# led7SegDriverWithPS.net
KiCad netlist of a schematic drawn in Altium Designer
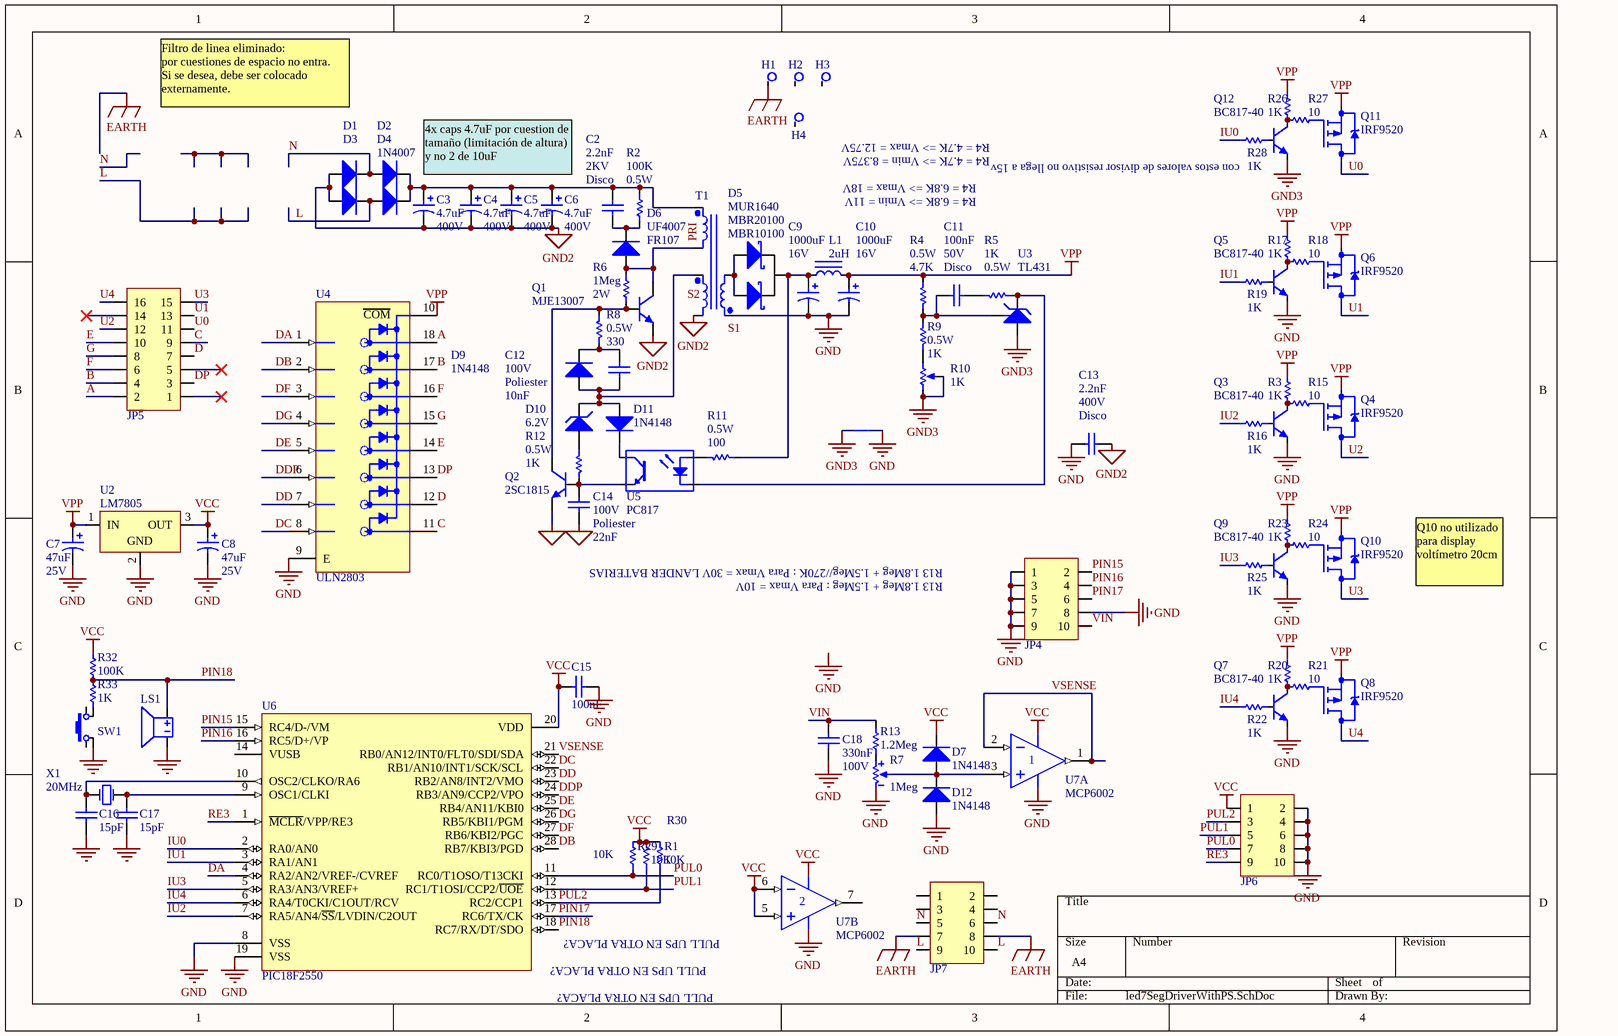
[diagram p0: led7SegDriverWithPS.SchDoc]

(export (version "E")
  (design (tool "Eeschema 10.0.6"))
  (components
    (comp (ref "C2")
      (value "2.2nF")
      (footprint "CAP200th")
      (description "Capacitor")
      (fields
        (field (name "VOLTAGE") "2KV")
        (field (name "TECHNOLOGY") "Disco")
        (field (name "Comment") "Cap")
      )
      (libsource (lib "FEDE") (part "Cap"))
    )
    (comp (ref "C3")
      (value "4.7uF")
      (footprint "cap10mm")
      (description "Capacitor Polarizado")
      (fields (field (name "VOLTAJE") "400V") (field (name "Comment") "Cap Pol"))
      (libsource (lib "FEDE") (part "Cap Pol"))
    )
    (comp (ref "C4")
      (value "4.7uF")
      (footprint "cap10mm")
      (description "Capacitor Polarizado")
      (fields (field (name "VOLTAJE") "400V") (field (name "Comment") "Cap Pol"))
      (libsource (lib "FEDE") (part "Cap Pol"))
    )
    (comp (ref "C5")
      (value "4.7uF")
      (footprint "cap10mm")
      (description "Capacitor Polarizado")
      (fields (field (name "VOLTAJE") "400V") (field (name "Comment") "Cap Pol"))
      (libsource (lib "FEDE") (part "Cap Pol"))
    )
    (comp (ref "C6")
      (value "4.7uF")
      (footprint "cap10mm")
      (description "Capacitor Polarizado")
      (fields (field (name "VOLTAJE") "400V") (field (name "Comment") "Cap Pol"))
      (libsource (lib "FEDE") (part "Cap Pol"))
    )
    (comp (ref "C7")
      (value "47uF")
      (footprint "Cap6.5mm")
      (description "Capacitor Polarizado")
      (fields (field (name "VOLTAJE") "25V") (field (name "Comment") "Cap Pol"))
      (libsource (lib "FEDE") (part "Cap Pol"))
    )
    (comp (ref "C8")
      (value "47uF")
      (footprint "Cap6.5mm")
      (description "Capacitor Polarizado")
      (fields (field (name "VOLTAJE") "25V") (field (name "Comment") "Cap Pol"))
      (libsource (lib "FEDE") (part "Cap Pol"))
    )
    (comp (ref "C9")
      (value "1000uF")
      (footprint "cap10mm")
      (description "Capacitor Polarizado")
      (fields (field (name "VOLTAJE") "16V") (field (name "Comment") "Cap Pol"))
      (libsource (lib "FEDE") (part "Cap Pol"))
    )
    (comp (ref "C10")
      (value "1000uF")
      (footprint "cap10mm")
      (description "Capacitor Polarizado")
      (fields (field (name "VOLTAJE") "16V") (field (name "Comment") "Cap Pol"))
      (libsource (lib "FEDE") (part "Cap Pol"))
    )
    (comp (ref "C11")
      (value "100nF")
      (footprint "C1206")
      (description "Capacitor")
      (fields
        (field (name "VOLTAGE") "50V")
        (field (name "TECHNOLOGY") "Disco")
        (field (name "Comment") "Cap")
      )
      (libsource (lib "FEDE") (part "Cap"))
    )
    (comp (ref "C12")
      (value "10nF")
      (footprint "CAP200th")
      (description "Capacitor")
      (fields
        (field (name "VOLTAGE") "100V")
        (field (name "TECHNOLOGY") "Poliester")
        (field (name "Comment") "Cap")
      )
      (libsource (lib "FEDE") (part "Cap"))
    )
    (comp (ref "C13")
      (value "2.2nF")
      (footprint "CAP200th")
      (description "Capacitor")
      (fields
        (field (name "VOLTAGE") "400V")
        (field (name "TECHNOLOGY") "Disco")
        (field (name "Comment") "Cap")
      )
      (libsource (lib "FEDE") (part "Cap"))
    )
    (comp (ref "C14")
      (value "22nF")
      (footprint "CAP200th")
      (description "Capacitor")
      (fields
        (field (name "VOLTAGE") "100V")
        (field (name "TECHNOLOGY") "Poliester")
        (field (name "Comment") "Cap")
      )
      (libsource (lib "FEDE") (part "Cap"))
    )
    (comp (ref "C15")
      (value "100nF")
      (footprint "1206NP")
      (description "Capacitor")
      (fields (field (name "VOLTAGE") "50V") (field (name "Comment") "Cap"))
      (libsource (lib "FEDE") (part "Cap"))
    )
    (comp (ref "C16")
      (value "15pF")
      (footprint "1206NP")
      (description "Capacitor")
      (fields (field (name "VOLTAGE") "50V") (field (name "Comment") "Cap"))
      (libsource (lib "FEDE") (part "Cap"))
    )
    (comp (ref "C17")
      (value "15pF")
      (footprint "1206NP")
      (description "Capacitor")
      (fields (field (name "VOLTAGE") "50V") (field (name "Comment") "Cap"))
      (libsource (lib "FEDE") (part "Cap"))
    )
    (comp (ref "C18")
      (value "330nF")
      (footprint "1206NP")
      (description "Capacitor")
      (fields (field (name "VOLTAGE") "100V") (field (name "Comment") "Cap"))
      (libsource (lib "FEDE") (part "Cap"))
    )
    (comp (ref "D1")
      (value "1N4007")
      (footprint "diode300_1mm")
      (description "1A 1000V General Purpose Rectifier")
      (libsource (lib "FEDE") (part "1N4007"))
    )
    (comp (ref "D2")
      (value "1N4007")
      (footprint "diode300_1mm")
      (description "1A 1000V General Purpose Rectifier")
      (libsource (lib "FEDE") (part "1N4007"))
    )
    (comp (ref "D3")
      (value "1N4007")
      (footprint "diode300_1mm")
      (description "1A 1000V General Purpose Rectifier")
      (libsource (lib "FEDE") (part "1N4007"))
    )
    (comp (ref "D4")
      (value "1N4007")
      (footprint "diode300_1mm")
      (description "1A 1000V General Purpose Rectifier")
      (libsource (lib "FEDE") (part "1N4007"))
    )
    (comp (ref "D5")
      (value "MBR20100")
      (footprint "TO220")
      (description "Schottky Diode 10A 45V")
      (fields (field (name "COMMENT2") "MBR10100") (field (name "ALTIUM_UNNAMED_1") "MUR1640"))
      (libsource (lib "FEDE") (part "MBR10100"))
    )
    (comp (ref "D6")
      (value "UF4007")
      (footprint "diode300_1mm")
      (description "1A 1000V General Purpose Rectifier")
      (fields (field (name "ALTERNATIVA") "FR107"))
      (libsource (lib "FEDE") (part "1N4007"))
    )
    (comp (ref "D7")
      (value "1N4148")
      (footprint "DSMD1MM")
      (description "High Conductance Fast Diode")
      (libsource (lib "FEDE") (part "1N4148"))
    )
    (comp (ref "D9")
      (value "1N4148")
      (footprint "DIODE300")
      (description "High Conductance Fast Diode")
      (libsource (lib "FEDE") (part "1N4148"))
    )
    (comp (ref "D10")
      (value "Zener")
      (footprint "DIODE300")
      (description "Zener Diode")
      (fields (field (name "VOLTAJE") "6.2V"))
      (libsource (lib "FEDE") (part "Zener"))
    )
    (comp (ref "D11")
      (value "1N4148")
      (footprint "DIODE300")
      (description "High Conductance Fast Diode")
      (libsource (lib "FEDE") (part "1N4148"))
    )
    (comp (ref "D12")
      (value "1N4148")
      (footprint "DSMD1MM")
      (description "High Conductance Fast Diode")
      (libsource (lib "FEDE") (part "1N4148"))
    )
    (comp (ref "H1")
      (value "Agujero de montaje")
      (footprint "agujero")
      (libsource (lib "FEDE") (part "Agujero de montaje"))
    )
    (comp (ref "H2")
      (value "Agujero de montaje")
      (footprint "agujero")
      (libsource (lib "FEDE") (part "Agujero de montaje"))
    )
    (comp (ref "H3")
      (value "Agujero de montaje")
      (footprint "agujero")
      (libsource (lib "FEDE") (part "Agujero de montaje"))
    )
    (comp (ref "H4")
      (value "Agujero de montaje")
      (footprint "agujero")
      (libsource (lib "FEDE") (part "Agujero de montaje"))
    )
    (comp (ref "JP4") (value "IDC 5x2") (footprint "idc5x2") (libsource (lib "FEDE") (part "IDC 5x2")))
    (comp (ref "JP5")
      (value "Header8x2")
      (footprint "idc8x2")
      (description "Header 8x2")
      (libsource (lib "FEDE") (part "Header8x2"))
    )
    (comp (ref "JP6") (value "IDC 5x2") (footprint "idc5x2") (libsource (lib "FEDE") (part "IDC 5x2")))
    (comp (ref "JP7") (value "IDC 5x2") (footprint "idc5x2") (libsource (lib "FEDE") (part "IDC 5x2")))
    (comp (ref "L1")
      (value "2uH")
      (footprint "ind8mm")
      (description "Inductor")
      (libsource (lib "FEDE") (part "Inductor"))
    )
    (comp (ref "LS1") (value "Buzzer") (footprint "buzzer12mm") (libsource (lib "FEDE") (part "Buzzer")))
    (comp (ref "Q1")
      (value "MJE13007")
      (footprint "TO220")
      (description "6A 100V NPN Bipolar Transistor")
      (libsource (lib "FEDE") (part "TIP41C"))
    )
    (comp (ref "Q2")
      (value "2SC1815")
      (footprint "to92")
      (description "NPN Bipolar Transistor")
      (libsource (lib "FEDE") (part "2SC1815"))
    )
    (comp (ref "Q3") (value "BC817-40") (footprint "SOT23") (libsource (lib "FEDE") (part "BC817-40")))
    (comp (ref "Q4")
      (value "IRF9520")
      (footprint "TO220")
      (description "100V  12A 0.3 ohm Power Field Effect Transistor")
      (libsource (lib "FEDE") (part "IRF9530"))
    )
    (comp (ref "Q5") (value "BC817-40") (footprint "SOT23") (libsource (lib "FEDE") (part "BC817-40")))
    (comp (ref "Q6")
      (value "IRF9520")
      (footprint "TO220")
      (description "100V  12A 0.3 ohm Power Field Effect Transistor")
      (libsource (lib "FEDE") (part "IRF9530"))
    )
    (comp (ref "Q7") (value "BC817-40") (footprint "SOT23") (libsource (lib "FEDE") (part "BC817-40")))
    (comp (ref "Q8")
      (value "IRF9520")
      (footprint "TO220")
      (description "100V  12A 0.3 ohm Power Field Effect Transistor")
      (libsource (lib "FEDE") (part "IRF9530"))
    )
    (comp (ref "Q9") (value "BC817-40") (footprint "SOT23") (libsource (lib "FEDE") (part "BC817-40")))
    (comp (ref "Q10")
      (value "IRF9520")
      (footprint "TO220")
      (description "100V  12A 0.3 ohm Power Field Effect Transistor")
      (libsource (lib "FEDE") (part "IRF9530"))
    )
    (comp (ref "Q11")
      (value "IRF9520")
      (footprint "TO220")
      (description "100V  12A 0.3 ohm Power Field Effect Transistor")
      (libsource (lib "FEDE") (part "IRF9530"))
    )
    (comp (ref "Q12") (value "BC817-40") (footprint "SOT23") (libsource (lib "FEDE") (part "BC817-40")))
    (comp (ref "R1")
      (value "Resistencia 1206; 10Kohm")
      (footprint "R1206")
      (fields (field (name "RESISTENCIA") "10K"))
      (libsource (lib "FEDE") (part "Resistencia 1206; 10Kohm"))
    )
    (comp (ref "R2")
      (value "100K")
      (footprint "RES300TH")
      (description "Resistor")
      (fields (field (name "POWER") "0.5W") (field (name "Comment") "Res"))
      (libsource (lib "FEDE") (part "Res"))
    )
    (comp (ref "R3")
      (value "Resistencia 1206; 1Kohm")
      (footprint "R1206")
      (fields (field (name "RESISTENCIA") "1K"))
      (libsource (lib "FEDE") (part "Resistencia 1206; 1Kohm"))
    )
    (comp (ref "R4")
      (value "4.7K")
      (footprint "RES300TH")
      (description "Resistor")
      (fields (field (name "POWER") "0.5W") (field (name "Comment") "Res"))
      (libsource (lib "FEDE") (part "Res"))
    )
    (comp (ref "R5")
      (value "1K")
      (footprint "R1206")
      (description "Resistor")
      (fields (field (name "POWER") "0.5W") (field (name "Comment") "Res"))
      (libsource (lib "FEDE") (part "Res"))
    )
    (comp (ref "R6")
      (value "1Meg")
      (footprint "res400th")
      (description "Resistor")
      (fields (field (name "POWER") "2W") (field (name "Comment") "Res"))
      (libsource (lib "FEDE") (part "Res"))
    )
    (comp (ref "R7")
      (value "1Meg")
      (footprint "PRESET")
      (description "Resistencia Variable")
      (fields (field (name "Comment") "Preset"))
      (libsource (lib "FEDE") (part "Preset"))
    )
    (comp (ref "R8")
      (value "330")
      (footprint "RES300TH")
      (description "Resistor")
      (fields (field (name "POWER") "0.5W") (field (name "Comment") "Res"))
      (libsource (lib "FEDE") (part "Res"))
    )
    (comp (ref "R9")
      (value "1K")
      (footprint "R1206")
      (description "Resistor")
      (fields (field (name "POWER") "0.5W") (field (name "Comment") "Res"))
      (libsource (lib "FEDE") (part "Res"))
    )
    (comp (ref "R10")
      (value "1K")
      (footprint "Preset6")
      (description "Resistencia Variable")
      (fields (field (name "Comment") "RVar"))
      (libsource (lib "FEDE") (part "RVar"))
    )
    (comp (ref "R11")
      (value "100")
      (footprint "RES300TH")
      (description "Resistor")
      (fields (field (name "POWER") "0.5W") (field (name "Comment") "Res"))
      (libsource (lib "FEDE") (part "Res"))
    )
    (comp (ref "R12")
      (value "1K")
      (footprint "RES300TH")
      (description "Resistor")
      (fields (field (name "POWER") "0.5W") (field (name "Comment") "Res"))
      (libsource (lib "FEDE") (part "Res"))
    )
    (comp (ref "R13")
      (value "1.2Meg")
      (footprint "1206NP")
      (description "Resistor")
      (fields (field (name "POWER") "0.25W") (field (name "Comment") "Res"))
      (libsource (lib "FEDE") (part "Res"))
    )
    (comp (ref "R14")
      (value "Resistencia 1206; 0ohm")
      (footprint "R1206")
      (libsource (lib "FEDE") (part "Resistencia 1206; 0ohm"))
    )
    (comp (ref "R15")
      (value "Resistencia 1206; 10ohm")
      (footprint "R1206")
      (fields (field (name "RESISTENCIA") "10"))
      (libsource (lib "FEDE") (part "Resistencia 1206; 10ohm"))
    )
    (comp (ref "R16")
      (value "Resistencia 1206; 1Kohm")
      (footprint "res300th")
      (fields (field (name "RESISTENCIA") "1K"))
      (libsource (lib "FEDE") (part "Resistencia 1206; 1Kohm"))
    )
    (comp (ref "R17")
      (value "Resistencia 1206; 1Kohm")
      (footprint "R1206")
      (fields (field (name "RESISTENCIA") "1K"))
      (libsource (lib "FEDE") (part "Resistencia 1206; 1Kohm"))
    )
    (comp (ref "R18")
      (value "Resistencia 1206; 10ohm")
      (footprint "R1206")
      (fields (field (name "RESISTENCIA") "10"))
      (libsource (lib "FEDE") (part "Resistencia 1206; 10ohm"))
    )
    (comp (ref "R19")
      (value "Resistencia 1206; 1Kohm")
      (footprint "res300th")
      (fields (field (name "RESISTENCIA") "1K"))
      (libsource (lib "FEDE") (part "Resistencia 1206; 1Kohm"))
    )
    (comp (ref "R20")
      (value "Resistencia 1206; 1Kohm")
      (footprint "R1206")
      (fields (field (name "RESISTENCIA") "1K"))
      (libsource (lib "FEDE") (part "Resistencia 1206; 1Kohm"))
    )
    (comp (ref "R21")
      (value "Resistencia 1206; 10ohm")
      (footprint "R1206")
      (fields (field (name "RESISTENCIA") "10"))
      (libsource (lib "FEDE") (part "Resistencia 1206; 10ohm"))
    )
    (comp (ref "R22")
      (value "Resistencia 1206; 1Kohm")
      (footprint "res300th")
      (fields (field (name "RESISTENCIA") "1K"))
      (libsource (lib "FEDE") (part "Resistencia 1206; 1Kohm"))
    )
    (comp (ref "R23")
      (value "Resistencia 1206; 1Kohm")
      (footprint "R1206")
      (fields (field (name "RESISTENCIA") "1K"))
      (libsource (lib "FEDE") (part "Resistencia 1206; 1Kohm"))
    )
    (comp (ref "R24")
      (value "Resistencia 1206; 10ohm")
      (footprint "R1206")
      (fields (field (name "RESISTENCIA") "10"))
      (libsource (lib "FEDE") (part "Resistencia 1206; 10ohm"))
    )
    (comp (ref "R25")
      (value "Resistencia 1206; 1Kohm")
      (footprint "res300th")
      (fields (field (name "RESISTENCIA") "1K"))
      (libsource (lib "FEDE") (part "Resistencia 1206; 1Kohm"))
    )
    (comp (ref "R26")
      (value "Resistencia 1206; 1Kohm")
      (footprint "R1206")
      (fields (field (name "RESISTENCIA") "1K"))
      (libsource (lib "FEDE") (part "Resistencia 1206; 1Kohm"))
    )
    (comp (ref "R27")
      (value "Resistencia 1206; 10ohm")
      (footprint "R1206")
      (fields (field (name "RESISTENCIA") "10"))
      (libsource (lib "FEDE") (part "Resistencia 1206; 10ohm"))
    )
    (comp (ref "R28")
      (value "Resistencia 1206; 1Kohm")
      (footprint "res300th")
      (fields (field (name "RESISTENCIA") "1K"))
      (libsource (lib "FEDE") (part "Resistencia 1206; 1Kohm"))
    )
    (comp (ref "R29")
      (value "Resistencia 1206; 10Kohm")
      (footprint "R1206")
      (fields (field (name "RESISTENCIA") "10K"))
      (libsource (lib "FEDE") (part "Resistencia 1206; 10Kohm"))
    )
    (comp (ref "R30")
      (value "Resistencia 1206; 10Kohm")
      (footprint "R1206")
      (fields (field (name "RESISTENCIA") "10K"))
      (libsource (lib "FEDE") (part "Resistencia 1206; 10Kohm"))
    )
    (comp (ref "R32")
      (value "Resistencia 1206; 10Kohm")
      (footprint "R1206")
      (fields (field (name "RESISTENCIA") "100K"))
      (libsource (lib "FEDE") (part "Resistencia 1206; 10Kohm"))
    )
    (comp (ref "R33")
      (value "Resistencia 1206; 10Kohm")
      (footprint "R1206")
      (fields (field (name "RESISTENCIA") "1K"))
      (libsource (lib "FEDE") (part "Resistencia 1206; 10Kohm"))
    )
    (comp (ref "SW1") (value "SW_T_5MM") (footprint "SW_T_5MM") (libsource (lib "FEDE") (part "SW_T_5MM")))
    (comp (ref "T1")
      (value "Transformer 2")
      (footprint "COSMO - EE 2507")
      (description "Three-winding Transformer")
      (fields (field (name "PUBLISHER") "Altium Limited"))
      (libsource (lib "FEDE") (part "Transformer 2"))
    )
    (comp (ref "U2")
      (value "LM7805")
      (footprint "TO220")
      (description "3-Terminal Positive Regulator")
      (libsource (lib "FEDE") (part "LM78XX (v1)"))
    )
    (comp (ref "U3")
      (value "TL431")
      (footprint "TO92")
      (description "Adjustable Zener Diode")
      (libsource (lib "FEDE") (part "TL431"))
    )
    (comp (ref "U4")
      (value "ULN2803")
      (footprint "DIP18Z")
      (description "Darlington Transistor Array")
      (libsource (lib "FEDE") (part "ULN2803"))
    )
    (comp (ref "U5")
      (value "PC817")
      (footprint "DIP4Z")
      (description "Optoaislador")
      (libsource (lib "FEDE") (part "PC817"))
    )
    (comp (ref "U6")
      (value "PIC18F2550")
      (footprint "DIP28Z2")
      (description "Enhanced FLASH Microcontroller")
      (libsource (lib "FEDE") (part "PIC18F2550"))
    )
    (comp (ref "U7")
      (value "MCP6002")
      (footprint "dip8z")
      (description "1 MHz Bandwidth Low Power Op Amp")
      (libsource (lib "FEDE") (part "MCP6002"))
    )
    (comp (ref "W1")
      (value "CABLE")
      (footprint "1206NP")
      (description "Cable")
      (libsource (lib "FEDE") (part "CABLE"))
    )
    (comp (ref "X1")
      (value "20MHz")
      (footprint "XTAL1")
      (description "Crystal Oscillator")
      (fields (field (name "Comment") "XTAL"))
      (libsource (lib "FEDE") (part "XTAL"))
    )
  )
  (nets
    (net (code "1") (name "/A") (class "Default")
      (node (ref "JP5") (pin "2") (pinfunction "2_2") (pintype "passive"))
      (node (ref "U4") (pin "18") (pinfunction "~{C}1_18") (pintype "open_collector"))
    )
    (net (code "2") (name "/B") (class "Default")
      (node (ref "JP5") (pin "4") (pinfunction "4_4") (pintype "passive"))
      (node (ref "U4") (pin "17") (pinfunction "~{C}2_17") (pintype "open_collector"))
    )
    (net (code "3") (name "/C") (class "Default")
      (node (ref "JP5") (pin "9") (pinfunction "9_9") (pintype "passive"))
      (node (ref "U4") (pin "11") (pinfunction "~{C}8_11") (pintype "open_collector"))
    )
    (net (code "4") (name "/D") (class "Default")
      (node (ref "JP5") (pin "7") (pinfunction "7_7") (pintype "passive"))
      (node (ref "U4") (pin "12") (pinfunction "~{C}7_12") (pintype "open_collector"))
    )
    (net (code "5") (name "/DA") (class "Default")
      (node (ref "U4") (pin "1") (pinfunction "B1_1") (pintype "input"))
      (node (ref "W1") (pin "1") (pinfunction "1_1") (pintype "passive"))
    )
    (net (code "6") (name "/DB") (class "Default")
      (node (ref "U4") (pin "2") (pinfunction "B2_2") (pintype "input"))
      (node (ref "U6") (pin "28") (pinfunction "RB7/KBI3/PGD_28") (pintype "bidirectional"))
    )
    (net (code "7") (name "/DC") (class "Default")
      (node (ref "U4") (pin "8") (pinfunction "B8_8") (pintype "input"))
      (node (ref "U6") (pin "22") (pinfunction "RB1/AN10/INT1/SCK/SCL_22") (pintype "bidirectional"))
    )
    (net (code "8") (name "/DD") (class "Default")
      (node (ref "U4") (pin "7") (pinfunction "B7_7") (pintype "input"))
      (node (ref "U6") (pin "23") (pinfunction "RB2/AN8/INT2/VMO_23") (pintype "bidirectional"))
    )
    (net (code "9") (name "/DDP") (class "Default")
      (node (ref "U4") (pin "6") (pinfunction "B6_6") (pintype "input"))
      (node (ref "U6") (pin "24") (pinfunction "RB3/AN9/CCP2/VPO_24") (pintype "bidirectional"))
    )
    (net (code "10") (name "/DE") (class "Default")
      (node (ref "U4") (pin "5") (pinfunction "B5_5") (pintype "input"))
      (node (ref "U6") (pin "25") (pinfunction "RB4/AN11/KBI0_25") (pintype "bidirectional"))
    )
    (net (code "11") (name "/DF") (class "Default")
      (node (ref "U4") (pin "3") (pinfunction "B3_3") (pintype "input"))
      (node (ref "U6") (pin "27") (pinfunction "RB6/KBI2/PGC_27") (pintype "bidirectional"))
    )
    (net (code "12") (name "/DG") (class "Default")
      (node (ref "U4") (pin "4") (pinfunction "B4_4") (pintype "input"))
      (node (ref "U6") (pin "26") (pinfunction "RB5/KBI1/PGM_26") (pintype "bidirectional"))
    )
    (net (code "13") (name "/DP") (class "Default")
      (node (ref "JP5") (pin "3") (pinfunction "3_3") (pintype "passive"))
      (node (ref "U4") (pin "13") (pinfunction "~{C}6_13") (pintype "open_collector"))
    )
    (net (code "14") (name "/E") (class "Default")
      (node (ref "JP5") (pin "10") (pinfunction "10_10") (pintype "passive"))
      (node (ref "U4") (pin "14") (pinfunction "~{C}5_14") (pintype "open_collector"))
    )
    (net (code "15") (name "/F") (class "Default")
      (node (ref "JP5") (pin "6") (pinfunction "6_6") (pintype "passive"))
      (node (ref "U4") (pin "16") (pinfunction "~{C}3_16") (pintype "open_collector"))
    )
    (net (code "16") (name "/G") (class "Default")
      (node (ref "JP5") (pin "8") (pinfunction "8_8") (pintype "passive"))
      (node (ref "U4") (pin "15") (pinfunction "~{C}4_15") (pintype "open_collector"))
    )
    (net (code "17") (name "/IU0") (class "Default")
      (node (ref "R28") (pin "1") (pinfunction "1_1") (pintype "passive"))
      (node (ref "U6") (pin "2") (pinfunction "RA0/AN0_2") (pintype "bidirectional"))
    )
    (net (code "18") (name "/IU1") (class "Default")
      (node (ref "R19") (pin "1") (pinfunction "1_1") (pintype "passive"))
      (node (ref "U6") (pin "3") (pinfunction "RA1/AN1_3") (pintype "bidirectional"))
    )
    (net (code "19") (name "/IU2") (class "Default")
      (node (ref "R16") (pin "1") (pinfunction "1_1") (pintype "passive"))
      (node (ref "U6") (pin "7") (pinfunction "RA5/AN4/~{SS}/LVDIN/C2OUT_7") (pintype "bidirectional"))
    )
    (net (code "20") (name "/IU3") (class "Default")
      (node (ref "R25") (pin "1") (pinfunction "1_1") (pintype "passive"))
      (node (ref "U6") (pin "5") (pinfunction "RA3/AN3/VREF+_5") (pintype "bidirectional"))
    )
    (net (code "21") (name "/IU4") (class "Default")
      (node (ref "R22") (pin "1") (pinfunction "1_1") (pintype "passive"))
      (node (ref "U6") (pin "6") (pinfunction "RA4/T0CKI/C1OUT/RCV_6") (pintype "bidirectional"))
    )
    (net (code "22") (name "/L") (class "Default")
      (node (ref "D2") (pin "2") (pinfunction "2_2") (pintype "passive"))
      (node (ref "D4") (pin "1") (pinfunction "1_1") (pintype "passive"))
      (node (ref "JP7") (pin "10") (pinfunction "10_10") (pintype "passive"))
      (node (ref "JP7") (pin "9") (pinfunction "9_9") (pintype "passive"))
    )
    (net (code "23") (name "/N") (class "Default")
      (node (ref "D1") (pin "2") (pinfunction "2_2") (pintype "passive"))
      (node (ref "D3") (pin "1") (pinfunction "1_1") (pintype "passive"))
      (node (ref "JP7") (pin "5") (pinfunction "5_5") (pintype "passive"))
      (node (ref "JP7") (pin "6") (pinfunction "6_6") (pintype "passive"))
    )
    (net (code "24") (name "/PIN15") (class "Default")
      (node (ref "JP4") (pin "2") (pinfunction "2_2") (pintype "passive"))
      (node (ref "U6") (pin "15") (pinfunction "RC4/D-/VM_15") (pintype "input"))
    )
    (net (code "25") (name "/PIN16") (class "Default")
      (node (ref "JP4") (pin "4") (pinfunction "4_4") (pintype "passive"))
      (node (ref "U6") (pin "16") (pinfunction "RC5/D+/VP_16") (pintype "input"))
    )
    (net (code "26") (name "/PIN17") (class "Default")
      (node (ref "JP4") (pin "6") (pinfunction "6_6") (pintype "passive"))
      (node (ref "U6") (pin "17") (pinfunction "RC6/TX/CK_17") (pintype "bidirectional"))
    )
    (net (code "27") (name "/PIN18") (class "Default")
      (node (ref "LS1") (pin "1") (pinfunction "1_1") (pintype "passive"))
      (node (ref "R32") (pin "1") (pinfunction "1_1") (pintype "passive"))
      (node (ref "R33") (pin "2") (pinfunction "2_2") (pintype "passive"))
      (node (ref "U6") (pin "18") (pinfunction "RC7/RX/DT/SDO_18") (pintype "bidirectional"))
    )
    (net (code "29") (name "/PUL0") (class "Default")
      (node (ref "JP6") (pin "7") (pinfunction "7_7") (pintype "passive"))
      (node (ref "R29") (pin "1") (pinfunction "1_1") (pintype "passive"))
      (node (ref "U6") (pin "11") (pinfunction "RC0/T1OSO/T13CKI_11") (pintype "bidirectional"))
    )
    (net (code "30") (name "/PUL1") (class "Default")
      (node (ref "JP6") (pin "5") (pinfunction "5_5") (pintype "passive"))
      (node (ref "R30") (pin "1") (pinfunction "1_1") (pintype "passive"))
      (node (ref "U6") (pin "12") (pinfunction "RC1/T1OSI/CCP2/~{UOE}_12") (pintype "bidirectional"))
    )
    (net (code "31") (name "/PUL2") (class "Default")
      (node (ref "JP6") (pin "3") (pinfunction "3_3") (pintype "passive"))
      (node (ref "R1") (pin "1") (pinfunction "1_1") (pintype "passive"))
      (node (ref "U6") (pin "13") (pinfunction "RC2/CCP1_13") (pintype "bidirectional"))
    )
    (net (code "32") (name "/RE3") (class "Default")
      (node (ref "JP6") (pin "9") (pinfunction "9_9") (pintype "passive"))
      (node (ref "U6") (pin "1") (pinfunction "~{MCLR}/VPP/RE3_1") (pintype "input"))
    )
    (net (code "35") (name "/U0") (class "Default")
      (node (ref "JP5") (pin "11") (pinfunction "11_11") (pintype "passive"))
      (node (ref "Q11") (pin "2") (pinfunction "D_2") (pintype "passive"))
    )
    (net (code "36") (name "/U1") (class "Default")
      (node (ref "JP5") (pin "13") (pinfunction "13_13") (pintype "passive"))
      (node (ref "Q6") (pin "2") (pinfunction "D_2") (pintype "passive"))
    )
    (net (code "37") (name "/U2") (class "Default")
      (node (ref "JP5") (pin "12") (pinfunction "12_12") (pintype "passive"))
      (node (ref "Q4") (pin "2") (pinfunction "D_2") (pintype "passive"))
    )
    (net (code "38") (name "/U3") (class "Default")
      (node (ref "JP5") (pin "15") (pinfunction "15_15") (pintype "passive"))
      (node (ref "Q10") (pin "2") (pinfunction "D_2") (pintype "passive"))
    )
    (net (code "39") (name "/U4") (class "Default")
      (node (ref "JP5") (pin "16") (pinfunction "16_16") (pintype "passive"))
      (node (ref "Q8") (pin "2") (pinfunction "D_2") (pintype "passive"))
    )
    (net (code "40") (name "/VIN") (class "Default")
      (node (ref "C18") (pin "2") (pinfunction "2_2") (pintype "passive"))
      (node (ref "JP4") (pin "10") (pinfunction "10_10") (pintype "passive"))
      (node (ref "R13") (pin "2") (pinfunction "2_2") (pintype "passive"))
    )
    (net (code "41") (name "/VSENSE") (class "Default")
      (node (ref "U6") (pin "21") (pinfunction "RB0/AN12/INT0/FLT0/SDI/SDA_21") (pintype "bidirectional"))
      (node (ref "U7") (pin "1") (pinfunction "OUT_1") (pintype "output"))
      (node (ref "U7") (pin "2") (pinfunction "IN-_2") (pintype "input"))
    )
    (net (code "42") (name "EARTH") (class "Default")
      (node (ref "H1") (pin "1") (pinfunction "1_1") (pintype "passive"))
      (node (ref "JP7") (pin "7") (pinfunction "7_7") (pintype "passive"))
      (node (ref "JP7") (pin "8") (pinfunction "8_8") (pintype "passive"))
    )
    (net (code "43") (name "GND") (class "Default")
      (node (ref "C10") (pin "2") (pinfunction "2_2") (pintype "passive"))
      (node (ref "C13") (pin "2") (pinfunction "2_2") (pintype "passive"))
      (node (ref "C15") (pin "2") (pinfunction "2_2") (pintype "passive"))
      (node (ref "C16") (pin "1") (pinfunction "1_1") (pintype "passive"))
      (node (ref "C17") (pin "1") (pinfunction "1_1") (pintype "passive"))
      (node (ref "C18") (pin "1") (pinfunction "1_1") (pintype "passive"))
      (node (ref "C7") (pin "2") (pinfunction "2_2") (pintype "passive"))
      (node (ref "C8") (pin "2") (pinfunction "2_2") (pintype "passive"))
      (node (ref "C9") (pin "2") (pinfunction "2_2") (pintype "passive"))
      (node (ref "D12") (pin "1") (pinfunction "1_1") (pintype "passive"))
      (node (ref "JP4") (pin "1") (pinfunction "1_1") (pintype "passive"))
      (node (ref "JP4") (pin "3") (pinfunction "3_3") (pintype "passive"))
      (node (ref "JP4") (pin "5") (pinfunction "5_5") (pintype "passive"))
      (node (ref "JP4") (pin "7") (pinfunction "7_7") (pintype "passive"))
      (node (ref "JP4") (pin "8") (pinfunction "8_8") (pintype "passive"))
      (node (ref "JP4") (pin "9") (pinfunction "9_9") (pintype "passive"))
      (node (ref "JP6") (pin "10") (pinfunction "10_10") (pintype "passive"))
      (node (ref "JP6") (pin "2") (pinfunction "2_2") (pintype "passive"))
      (node (ref "JP6") (pin "4") (pinfunction "4_4") (pintype "passive"))
      (node (ref "JP6") (pin "6") (pinfunction "6_6") (pintype "passive"))
      (node (ref "JP6") (pin "8") (pinfunction "8_8") (pintype "passive"))
      (node (ref "LS1") (pin "2") (pinfunction "2_2") (pintype "passive"))
      (node (ref "Q3") (pin "2") (pinfunction "E_2") (pintype "passive"))
      (node (ref "Q5") (pin "2") (pinfunction "E_2") (pintype "passive"))
      (node (ref "Q7") (pin "2") (pinfunction "E_2") (pintype "passive"))
      (node (ref "Q9") (pin "2") (pinfunction "E_2") (pintype "passive"))
      (node (ref "R14") (pin "2") (pinfunction "2_2") (pintype "passive"))
      (node (ref "R7") (pin "3") (pinfunction "3_3") (pintype "passive"))
      (node (ref "SW1") (pin "2") (pinfunction "2_2") (pintype "passive"))
      (node (ref "T1") (pin "1") (pinfunction "1_1") (pintype "passive"))
      (node (ref "U2") (pin "2") (pinfunction "GND_2") (pintype "power_in"))
      (node (ref "U4") (pin "9") (pinfunction "E_9") (pintype "power_in"))
      (node (ref "U6") (pin "19") (pinfunction "VSS_19") (pintype "power_in"))
      (node (ref "U6") (pin "8") (pinfunction "VSS_8") (pintype "power_in"))
      (node (ref "U7") (pin "4") (pinfunction "V-_4") (pintype "power_in"))
    )
    (net (code "44") (name "GND2") (class "Default")
      (node (ref "C13") (pin "1") (pinfunction "1_1") (pintype "passive"))
      (node (ref "C14") (pin "1") (pinfunction "1_1") (pintype "passive"))
      (node (ref "C3") (pin "2") (pinfunction "2_2") (pintype "passive"))
      (node (ref "C4") (pin "2") (pinfunction "2_2") (pintype "passive"))
      (node (ref "C5") (pin "2") (pinfunction "2_2") (pintype "passive"))
      (node (ref "C6") (pin "2") (pinfunction "2_2") (pintype "passive"))
      (node (ref "D1") (pin "1") (pinfunction "1_1") (pintype "passive"))
      (node (ref "D2") (pin "1") (pinfunction "1_1") (pintype "passive"))
      (node (ref "Q1") (pin "3") (pinfunction "E_3") (pintype "passive"))
      (node (ref "Q2") (pin "1") (pinfunction "E_1") (pintype "passive"))
      (node (ref "T1") (pin "4") (pinfunction "4_4") (pintype "passive"))
    )
    (net (code "45") (name "GND3") (class "Default")
      (node (ref "Q12") (pin "2") (pinfunction "E_2") (pintype "passive"))
      (node (ref "R10") (pin "1") (pinfunction "1_1") (pintype "passive"))
      (node (ref "R10") (pin "3") (pinfunction "3_3") (pintype "passive"))
      (node (ref "R14") (pin "1") (pinfunction "1_1") (pintype "passive"))
      (node (ref "U3") (pin "2") (pinfunction "A_2") (pintype "passive"))
    )
    (net (code "46") (name "Net-(C2-Pad1)") (class "Default")
      (node (ref "C2") (pin "1") (pinfunction "1_1") (pintype "passive"))
      (node (ref "D6") (pin "2") (pinfunction "2_2") (pintype "passive"))
      (node (ref "R2") (pin "2") (pinfunction "2_2") (pintype "passive"))
    )
    (net (code "47") (name "Net-(C2-Pad2)") (class "Default")
      (node (ref "C2") (pin "2") (pinfunction "2_2") (pintype "passive"))
      (node (ref "C3") (pin "1") (pinfunction "1_1") (pintype "passive"))
      (node (ref "C4") (pin "1") (pinfunction "1_1") (pintype "passive"))
      (node (ref "C5") (pin "1") (pinfunction "1_1") (pintype "passive"))
      (node (ref "C6") (pin "1") (pinfunction "1_1") (pintype "passive"))
      (node (ref "D3") (pin "2") (pinfunction "2_2") (pintype "passive"))
      (node (ref "D4") (pin "2") (pinfunction "2_2") (pintype "passive"))
      (node (ref "R2") (pin "1") (pinfunction "1_1") (pintype "passive"))
      (node (ref "T1") (pin "5") (pinfunction "5_5") (pintype "passive"))
    )
    (net (code "48") (name "Net-(C11-Pad1)") (class "Default")
      (node (ref "C11") (pin "1") (pinfunction "1_1") (pintype "passive"))
      (node (ref "R5") (pin "1") (pinfunction "1_1") (pintype "passive"))
    )
    (net (code "49") (name "Net-(C12-Pad2)") (class "Default")
      (node (ref "C12") (pin "2") (pinfunction "2_2") (pintype "passive"))
      (node (ref "D9") (pin "2") (pinfunction "2_2") (pintype "passive"))
      (node (ref "R8") (pin "1") (pinfunction "1_1") (pintype "passive"))
    )
    (net (code "50") (name "Net-(D5-A-Pad1)") (class "Default")
      (node (ref "D5") (pin "1") (pinfunction "A_1") (pintype "passive"))
      (node (ref "D5") (pin "3") (pinfunction "A_3") (pintype "passive"))
      (node (ref "T1") (pin "2") (pinfunction "2_2") (pintype "passive"))
    )
    (net (code "51") (name "Net-(D5-K)") (class "Default")
      (node (ref "C9") (pin "1") (pinfunction "1_1") (pintype "passive"))
      (node (ref "D5") (pin "2") (pinfunction "K_2") (pintype "passive"))
      (node (ref "L1") (pin "1") (pinfunction "1_1") (pintype "passive"))
      (node (ref "R11") (pin "1") (pinfunction "1_1") (pintype "passive"))
    )
    (net (code "52") (name "Net-(D10-A)") (class "Default")
      (node (ref "D10") (pin "1") (pinfunction "A_1") (pintype "passive"))
      (node (ref "R12") (pin "2") (pinfunction "2_2") (pintype "passive"))
    )
    (net (code "53") (name "Net-(D10-K)") (class "Default")
      (node (ref "C12") (pin "1") (pinfunction "1_1") (pintype "passive"))
      (node (ref "D10") (pin "2") (pinfunction "K_2") (pintype "passive"))
      (node (ref "D11") (pin "1") (pinfunction "1_1") (pintype "passive"))
      (node (ref "D9") (pin "1") (pinfunction "1_1") (pintype "passive"))
      (node (ref "T1") (pin "3") (pinfunction "3_3") (pintype "passive"))
    )
    (net (code "54") (name "Net-(Q1-B)") (class "Default")
      (node (ref "Q1") (pin "2") (pinfunction "B_2") (pintype "passive"))
      (node (ref "Q2") (pin "2") (pinfunction "C_2") (pintype "passive"))
      (node (ref "R6") (pin "2") (pinfunction "2_2") (pintype "passive"))
      (node (ref "R8") (pin "2") (pinfunction "2_2") (pintype "passive"))
    )
    (net (code "55") (name "Net-(Q1-C)") (class "Default")
      (node (ref "D6") (pin "1") (pinfunction "1_1") (pintype "passive"))
      (node (ref "Q1") (pin "1") (pinfunction "C_1") (pintype "passive"))
      (node (ref "R6") (pin "1") (pinfunction "1_1") (pintype "passive"))
      (node (ref "T1") (pin "6") (pinfunction "6_6") (pintype "passive"))
    )
    (net (code "56") (name "Net-(Q2-B)") (class "Default")
      (node (ref "C14") (pin "2") (pinfunction "2_2") (pintype "passive"))
      (node (ref "Q2") (pin "3") (pinfunction "B_3") (pintype "passive"))
      (node (ref "R12") (pin "1") (pinfunction "1_1") (pintype "passive"))
      (node (ref "U5") (pin "3") (pinfunction "E_3") (pintype "passive"))
    )
    (net (code "57") (name "Net-(Q3-B)") (class "Default")
      (node (ref "Q3") (pin "1") (pinfunction "B_1") (pintype "passive"))
      (node (ref "R16") (pin "2") (pinfunction "2_2") (pintype "passive"))
    )
    (net (code "58") (name "Net-(Q3-C)") (class "Default")
      (node (ref "Q3") (pin "3") (pinfunction "C_3") (pintype "passive"))
      (node (ref "R15") (pin "1") (pinfunction "1_1") (pintype "passive"))
      (node (ref "R3") (pin "1") (pinfunction "1_1") (pintype "passive"))
    )
    (net (code "59") (name "Net-(Q4-G)") (class "Default")
      (node (ref "Q4") (pin "1") (pinfunction "G_1") (pintype "passive"))
      (node (ref "R15") (pin "2") (pinfunction "2_2") (pintype "passive"))
    )
    (net (code "60") (name "Net-(Q5-B)") (class "Default")
      (node (ref "Q5") (pin "1") (pinfunction "B_1") (pintype "passive"))
      (node (ref "R19") (pin "2") (pinfunction "2_2") (pintype "passive"))
    )
    (net (code "61") (name "Net-(Q5-C)") (class "Default")
      (node (ref "Q5") (pin "3") (pinfunction "C_3") (pintype "passive"))
      (node (ref "R17") (pin "1") (pinfunction "1_1") (pintype "passive"))
      (node (ref "R18") (pin "1") (pinfunction "1_1") (pintype "passive"))
    )
    (net (code "62") (name "Net-(Q6-G)") (class "Default")
      (node (ref "Q6") (pin "1") (pinfunction "G_1") (pintype "passive"))
      (node (ref "R18") (pin "2") (pinfunction "2_2") (pintype "passive"))
    )
    (net (code "63") (name "Net-(Q7-B)") (class "Default")
      (node (ref "Q7") (pin "1") (pinfunction "B_1") (pintype "passive"))
      (node (ref "R22") (pin "2") (pinfunction "2_2") (pintype "passive"))
    )
    (net (code "64") (name "Net-(Q7-C)") (class "Default")
      (node (ref "Q7") (pin "3") (pinfunction "C_3") (pintype "passive"))
      (node (ref "R20") (pin "1") (pinfunction "1_1") (pintype "passive"))
      (node (ref "R21") (pin "1") (pinfunction "1_1") (pintype "passive"))
    )
    (net (code "65") (name "Net-(Q8-G)") (class "Default")
      (node (ref "Q8") (pin "1") (pinfunction "G_1") (pintype "passive"))
      (node (ref "R21") (pin "2") (pinfunction "2_2") (pintype "passive"))
    )
    (net (code "66") (name "Net-(Q9-B)") (class "Default")
      (node (ref "Q9") (pin "1") (pinfunction "B_1") (pintype "passive"))
      (node (ref "R25") (pin "2") (pinfunction "2_2") (pintype "passive"))
    )
    (net (code "67") (name "Net-(Q9-C)") (class "Default")
      (node (ref "Q9") (pin "3") (pinfunction "C_3") (pintype "passive"))
      (node (ref "R23") (pin "1") (pinfunction "1_1") (pintype "passive"))
      (node (ref "R24") (pin "1") (pinfunction "1_1") (pintype "passive"))
    )
    (net (code "68") (name "Net-(Q10-G)") (class "Default")
      (node (ref "Q10") (pin "1") (pinfunction "G_1") (pintype "passive"))
      (node (ref "R24") (pin "2") (pinfunction "2_2") (pintype "passive"))
    )
    (net (code "69") (name "Net-(Q11-G)") (class "Default")
      (node (ref "Q11") (pin "1") (pinfunction "G_1") (pintype "passive"))
      (node (ref "R27") (pin "2") (pinfunction "2_2") (pintype "passive"))
    )
    (net (code "70") (name "Net-(Q12-B)") (class "Default")
      (node (ref "Q12") (pin "1") (pinfunction "B_1") (pintype "passive"))
      (node (ref "R28") (pin "2") (pinfunction "2_2") (pintype "passive"))
    )
    (net (code "71") (name "Net-(Q12-C)") (class "Default")
      (node (ref "Q12") (pin "3") (pinfunction "C_3") (pintype "passive"))
      (node (ref "R26") (pin "1") (pinfunction "1_1") (pintype "passive"))
      (node (ref "R27") (pin "1") (pinfunction "1_1") (pintype "passive"))
    )
    (net (code "72") (name "Net-(R10-Pad2)") (class "Default")
      (node (ref "R10") (pin "2") (pinfunction "2_2") (pintype "passive"))
      (node (ref "R9") (pin "2") (pinfunction "2_2") (pintype "passive"))
    )
    (net (code "73") (name "Net-(R13-Pad1)") (class "Default")
      (node (ref "R13") (pin "1") (pinfunction "1_1") (pintype "passive"))
      (node (ref "R7") (pin "1") (pinfunction "1_1") (pintype "passive"))
    )
    (net (code "74") (name "Net-(R33-Pad1)") (class "Default")
      (node (ref "R33") (pin "1") (pinfunction "1_1") (pintype "passive"))
      (node (ref "SW1") (pin "1") (pinfunction "1_1") (pintype "passive"))
    )
    (net (code "75") (name "Net-(U3-K)") (class "Default")
      (node (ref "R5") (pin "2") (pinfunction "2_2") (pintype "passive"))
      (node (ref "U3") (pin "1") (pinfunction "K_1") (pintype "passive"))
      (node (ref "U5") (pin "2") (pinfunction "K_2") (pintype "passive"))
    )
    (net (code "76") (name "Net-(U3-REF)") (class "Default")
      (node (ref "C11") (pin "2") (pinfunction "2_2") (pintype "passive"))
      (node (ref "R4") (pin "2") (pinfunction "2_2") (pintype "passive"))
      (node (ref "R9") (pin "1") (pinfunction "1_1") (pintype "passive"))
      (node (ref "U3") (pin "3") (pinfunction "REF_3") (pintype "passive"))
    )
    (net (code "77") (name "Net-(U5-A)") (class "Default")
      (node (ref "R11") (pin "2") (pinfunction "2_2") (pintype "passive"))
      (node (ref "U5") (pin "1") (pinfunction "A_1") (pintype "passive"))
    )
    (net (code "78") (name "Net-(U5-C)") (class "Default")
      (node (ref "D11") (pin "2") (pinfunction "2_2") (pintype "passive"))
      (node (ref "U5") (pin "4") (pinfunction "C_4") (pintype "passive"))
    )
    (net (code "79") (name "Net-(U6-OSC1{slash}CLKI)") (class "Default")
      (node (ref "C17") (pin "2") (pinfunction "2_2") (pintype "passive"))
      (node (ref "U6") (pin "9") (pinfunction "OSC1/CLKI_9") (pintype "input"))
      (node (ref "X1") (pin "2") (pinfunction "OSC2_2") (pintype "passive"))
    )
    (net (code "80") (name "Net-(U6-OSC2{slash}CLKO{slash}RA6)") (class "Default")
      (node (ref "C16") (pin "2") (pinfunction "2_2") (pintype "passive"))
      (node (ref "U6") (pin "10") (pinfunction "OSC2/CLKO/RA6_10") (pintype "output"))
      (node (ref "X1") (pin "1") (pinfunction "OSC1_1") (pintype "passive"))
    )
    (net (code "81") (name "Net-(U6-RA2{slash}AN2{slash}VREF-{slash}CVREF)") (class "Default")
      (node (ref "U6") (pin "4") (pinfunction "RA2/AN2/VREF-/CVREF_4") (pintype "bidirectional"))
      (node (ref "W1") (pin "2") (pinfunction "2_2") (pintype "passive"))
    )
    (net (code "82") (name "Net-(U7A-IN+)") (class "Default")
      (node (ref "D12") (pin "2") (pinfunction "2_2") (pintype "passive"))
      (node (ref "D7") (pin "1") (pinfunction "1_1") (pintype "passive"))
      (node (ref "R7") (pin "2") (pinfunction "2_2") (pintype "passive"))
      (node (ref "U7") (pin "3") (pinfunction "IN+_3") (pintype "input"))
    )
    (net (code "83") (name "VCC") (class "Default")
      (node (ref "C15") (pin "1") (pinfunction "1_1") (pintype "passive"))
      (node (ref "C8") (pin "1") (pinfunction "1_1") (pintype "passive"))
      (node (ref "D7") (pin "2") (pinfunction "2_2") (pintype "passive"))
      (node (ref "JP6") (pin "1") (pinfunction "1_1") (pintype "passive"))
      (node (ref "R1") (pin "2") (pinfunction "2_2") (pintype "passive"))
      (node (ref "R29") (pin "2") (pinfunction "2_2") (pintype "passive"))
      (node (ref "R30") (pin "2") (pinfunction "2_2") (pintype "passive"))
      (node (ref "R32") (pin "2") (pinfunction "2_2") (pintype "passive"))
      (node (ref "U2") (pin "3") (pinfunction "OUT_3") (pintype "power_in"))
      (node (ref "U6") (pin "20") (pinfunction "VDD_20") (pintype "power_in"))
      (node (ref "U7") (pin "5") (pinfunction "IN+_5") (pintype "input"))
      (node (ref "U7") (pin "6") (pinfunction "IN-_6") (pintype "input"))
      (node (ref "U7") (pin "8") (pinfunction "V+_8") (pintype "power_in"))
    )
    (net (code "84") (name "VPP") (class "Default")
      (node (ref "C10") (pin "1") (pinfunction "1_1") (pintype "passive"))
      (node (ref "C7") (pin "1") (pinfunction "1_1") (pintype "passive"))
      (node (ref "L1") (pin "2") (pinfunction "2_2") (pintype "passive"))
      (node (ref "Q10") (pin "3") (pinfunction "S_3") (pintype "passive"))
      (node (ref "Q11") (pin "3") (pinfunction "S_3") (pintype "passive"))
      (node (ref "Q4") (pin "3") (pinfunction "S_3") (pintype "passive"))
      (node (ref "Q6") (pin "3") (pinfunction "S_3") (pintype "passive"))
      (node (ref "Q8") (pin "3") (pinfunction "S_3") (pintype "passive"))
      (node (ref "R17") (pin "2") (pinfunction "2_2") (pintype "passive"))
      (node (ref "R20") (pin "2") (pinfunction "2_2") (pintype "passive"))
      (node (ref "R23") (pin "2") (pinfunction "2_2") (pintype "passive"))
      (node (ref "R26") (pin "2") (pinfunction "2_2") (pintype "passive"))
      (node (ref "R3") (pin "2") (pinfunction "2_2") (pintype "passive"))
      (node (ref "R4") (pin "1") (pinfunction "1_1") (pintype "passive"))
      (node (ref "U2") (pin "1") (pinfunction "IN_1") (pintype "power_in"))
      (node (ref "U4") (pin "10") (pinfunction "~{COM}_10") (pintype "passive"))
    )
    (net (code "85") (name "unconnected-(H2-Pad1)") (class "Default")
      (node (ref "H2") (pin "1") (pinfunction "1_1") (pintype "passive"))
    )
    (net (code "86") (name "unconnected-(H3-Pad1)") (class "Default")
      (node (ref "H3") (pin "1") (pinfunction "1_1") (pintype "passive"))
    )
    (net (code "87") (name "unconnected-(H4-Pad1)") (class "Default")
      (node (ref "H4") (pin "1") (pinfunction "1_1") (pintype "passive"))
    )
    (net (code "88") (name "unconnected-(JP5-Pad1)") (class "Default")
      (node (ref "JP5") (pin "1") (pinfunction "1_1") (pintype "passive+no_connect"))
    )
    (net (code "89") (name "unconnected-(JP5-Pad5)") (class "Default")
      (node (ref "JP5") (pin "5") (pinfunction "5_5") (pintype "passive+no_connect"))
    )
    (net (code "90") (name "unconnected-(JP5-Pad14)") (class "Default")
      (node (ref "JP5") (pin "14") (pinfunction "14_14") (pintype "passive+no_connect"))
    )
    (net (code "91") (name "unconnected-(JP7-Pad1)") (class "Default")
      (node (ref "JP7") (pin "1") (pinfunction "1_1") (pintype "passive"))
    )
    (net (code "92") (name "unconnected-(JP7-Pad2)") (class "Default")
      (node (ref "JP7") (pin "2") (pinfunction "2_2") (pintype "passive"))
    )
    (net (code "93") (name "unconnected-(JP7-Pad3)") (class "Default")
      (node (ref "JP7") (pin "3") (pinfunction "3_3") (pintype "passive"))
    )
    (net (code "94") (name "unconnected-(JP7-Pad4)") (class "Default")
      (node (ref "JP7") (pin "4") (pinfunction "4_4") (pintype "passive"))
    )
    (net (code "95") (name "unconnected-(SW1-Pad3)") (class "Default")
      (node (ref "SW1") (pin "3") (pinfunction "3_3") (pintype "passive"))
    )
    (net (code "96") (name "unconnected-(SW1-Pad4)") (class "Default")
      (node (ref "SW1") (pin "4") (pinfunction "4_4") (pintype "passive"))
    )
    (net (code "97") (name "unconnected-(U6-VUSB-Pad14)") (class "Default")
      (node (ref "U6") (pin "14") (pinfunction "VUSB_14") (pintype "passive"))
    )
    (net (code "98") (name "unconnected-(U7B-OUT-Pad7)") (class "Default")
      (node (ref "U7") (pin "7") (pinfunction "OUT_7") (pintype "output"))
    )
  )
)
